# LEDboard_v0_3-R001.net
KiCad netlist of a schematic drawn in EAGLE
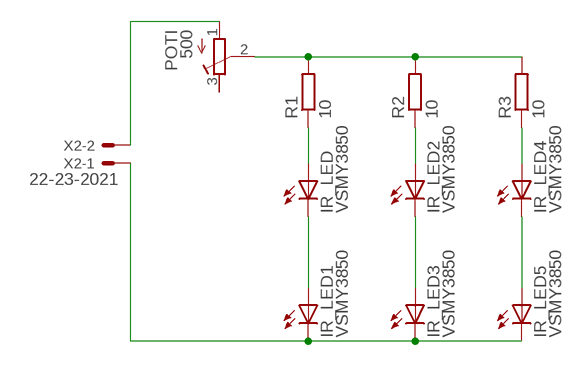
[diagram p0: schematic, sheet 1]

(export (version "E")
  (design (tool "Eeschema 10.0.6"))
  (components
    (comp (ref "IR_LED")
      (value "VSMY3850")
      (footprint "eagle-import:VSMY3850X")
      (libsource (lib "eagle-import") (part "VSMY3850"))
    )
    (comp (ref "IR_LED1")
      (value "VSMY3850")
      (footprint "eagle-import:VSMY3850X")
      (libsource (lib "eagle-import") (part "VSMY3850"))
    )
    (comp (ref "IR_LED2")
      (value "VSMY3850")
      (footprint "eagle-import:VSMY3850X")
      (libsource (lib "eagle-import") (part "VSMY3850"))
    )
    (comp (ref "IR_LED3")
      (value "VSMY3850")
      (footprint "eagle-import:VSMY3850X")
      (libsource (lib "eagle-import") (part "VSMY3850"))
    )
    (comp (ref "IR_LED4")
      (value "VSMY3850")
      (footprint "eagle-import:VSMY3850X")
      (libsource (lib "eagle-import") (part "VSMY3850"))
    )
    (comp (ref "IR_LED5")
      (value "VSMY3850")
      (footprint "eagle-import:VSMY3850X")
      (libsource (lib "eagle-import") (part "VSMY3850"))
    )
    (comp (ref "POTI")
      (value "500")
      (footprint "eagle-import:RTRIM64Y")
      (libsource (lib "eagle-import") (part "R-TRIMM64Y"))
    )
    (comp (ref "R1")
      (value "10")
      (footprint "eagle-import:R0805")
      (libsource (lib "eagle-import") (part "R-EU_R0805"))
    )
    (comp (ref "R2")
      (value "10")
      (footprint "eagle-import:R0805")
      (libsource (lib "eagle-import") (part "R-EU_R0805"))
    )
    (comp (ref "R3")
      (value "10")
      (footprint "eagle-import:R0805")
      (libsource (lib "eagle-import") (part "R-EU_R0805"))
    )
    (comp (ref "X2")
      (value "22-23-2021")
      (footprint "eagle-import:22-23-2021")
      (fields (field (name "MF") "MOLEX"))
      (libsource (lib "eagle-import") (part "22-23-2021"))
    )
  )
  (nets
    (net (code "1") (name "Net-(IR_LED-A)") (class "Default")
      (node (ref "IR_LED") (pin "1") (pinfunction "A_1") (pintype "passive"))
      (node (ref "R1") (pin "1") (pinfunction "1_1") (pintype "passive"))
    )
    (net (code "2") (name "Net-(IR_LED-C)") (class "Default")
      (node (ref "IR_LED") (pin "2") (pinfunction "C_2") (pintype "passive"))
      (node (ref "IR_LED1") (pin "1") (pinfunction "A_1") (pintype "passive"))
    )
    (net (code "3") (name "Net-(IR_LED1-C)") (class "Default")
      (node (ref "IR_LED1") (pin "2") (pinfunction "C_2") (pintype "passive"))
      (node (ref "IR_LED3") (pin "2") (pinfunction "C_2") (pintype "passive"))
      (node (ref "IR_LED5") (pin "2") (pinfunction "C_2") (pintype "passive"))
      (node (ref "X2") (pin "1") (pinfunction "S_1") (pintype "passive"))
    )
    (net (code "4") (name "Net-(IR_LED2-A)") (class "Default")
      (node (ref "IR_LED2") (pin "1") (pinfunction "A_1") (pintype "passive"))
      (node (ref "R2") (pin "1") (pinfunction "1_1") (pintype "passive"))
    )
    (net (code "5") (name "Net-(IR_LED2-C)") (class "Default")
      (node (ref "IR_LED2") (pin "2") (pinfunction "C_2") (pintype "passive"))
      (node (ref "IR_LED3") (pin "1") (pinfunction "A_1") (pintype "passive"))
    )
    (net (code "6") (name "Net-(IR_LED4-A)") (class "Default")
      (node (ref "IR_LED4") (pin "1") (pinfunction "A_1") (pintype "passive"))
      (node (ref "R3") (pin "1") (pinfunction "1_1") (pintype "passive"))
    )
    (net (code "7") (name "Net-(IR_LED4-C)") (class "Default")
      (node (ref "IR_LED4") (pin "2") (pinfunction "C_2") (pintype "passive"))
      (node (ref "IR_LED5") (pin "1") (pinfunction "A_1") (pintype "passive"))
    )
    (net (code "8") (name "Net-(POTI-A)") (class "Default")
      (node (ref "POTI") (pin "1") (pinfunction "A_1") (pintype "passive"))
      (node (ref "X2") (pin "2") (pinfunction "S_2") (pintype "passive"))
    )
    (net (code "9") (name "Net-(POTI-S)") (class "Default")
      (node (ref "POTI") (pin "2") (pinfunction "S_2") (pintype "passive"))
      (node (ref "R1") (pin "2") (pinfunction "2_2") (pintype "passive"))
      (node (ref "R2") (pin "2") (pinfunction "2_2") (pintype "passive"))
      (node (ref "R3") (pin "2") (pinfunction "2_2") (pintype "passive"))
    )
    (net (code "10") (name "unconnected-(POTI-E-Pad3)") (class "Default")
      (node (ref "POTI") (pin "3") (pinfunction "E_3") (pintype "passive"))
    )
  )
)
